# Flyback_schematic.net
KiCad netlist of a schematic drawn in Altium Designer
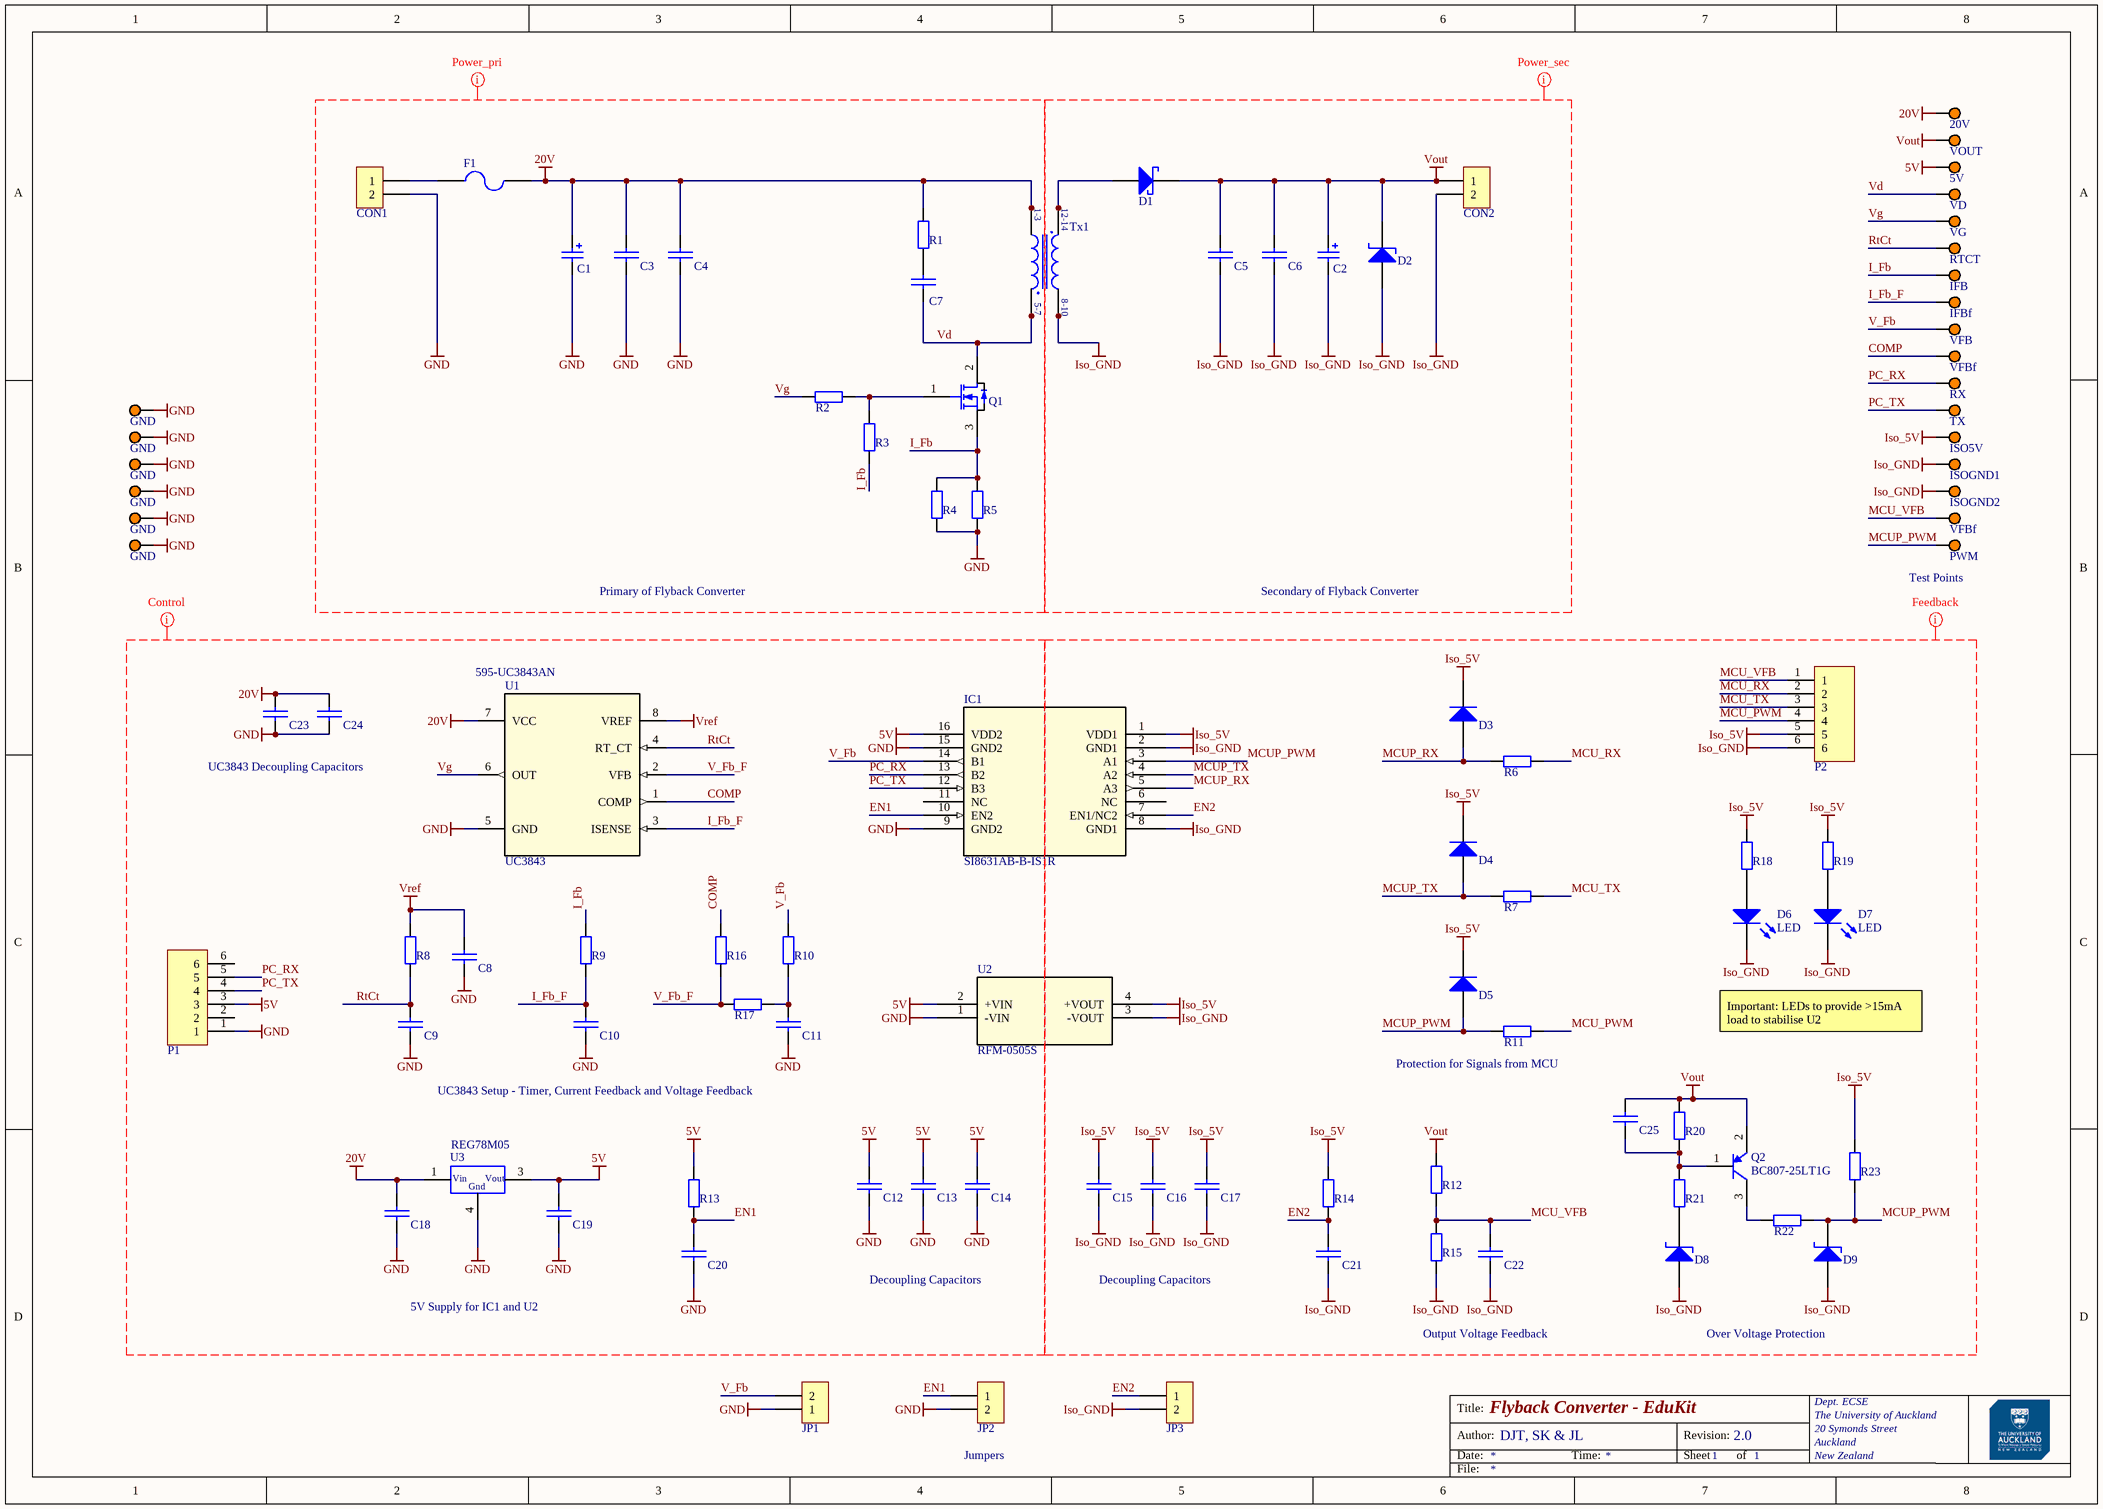
[diagram p0: Flyback_schematic.SchDoc]

(export (version "E")
  (design (tool "Eeschema 10.0.6"))
  (components
    (comp (ref "C1") (value "ECAP") (footprint "CR05") (libsource (lib "EE311_library") (part "ECAP")))
    (comp (ref "C2") (value "ECAP") (footprint "CR05") (libsource (lib "EE311_library") (part "ECAP")))
    (comp (ref "C3")
      (value "CCAP1210")
      (footprint "C1210")
      (libsource (lib "EE311_library") (part "CCAP1210"))
    )
    (comp (ref "C4")
      (value "CCAP1210")
      (footprint "C1210")
      (libsource (lib "EE311_library") (part "CCAP1210"))
    )
    (comp (ref "C5")
      (value "CCAP1210")
      (footprint "C1210")
      (libsource (lib "EE311_library") (part "CCAP1210"))
    )
    (comp (ref "C6")
      (value "CCAP1210")
      (footprint "C1210")
      (libsource (lib "EE311_library") (part "CCAP1210"))
    )
    (comp (ref "C7")
      (value "CCAP1210")
      (footprint "C1210")
      (libsource (lib "EE311_library") (part "CCAP1210"))
    )
    (comp (ref "C8")
      (value "Capacitor 0805")
      (footprint "C0805")
      (description "CCAP0805")
      (libsource (lib "EE311_library") (part "CCAP0805"))
    )
    (comp (ref "C9")
      (value "Capacitor 0805")
      (footprint "C0805")
      (description "CCAP0805")
      (libsource (lib "EE311_library") (part "CCAP0805"))
    )
    (comp (ref "C10")
      (value "Capacitor 0805")
      (footprint "C0805")
      (description "CCAP0805")
      (libsource (lib "EE311_library") (part "CCAP0805"))
    )
    (comp (ref "C11")
      (value "Capacitor 0805")
      (footprint "C0805")
      (description "CCAP0805")
      (libsource (lib "EE311_library") (part "CCAP0805"))
    )
    (comp (ref "C12")
      (value "Capacitor 0805")
      (footprint "C0805")
      (description "CCAP0805")
      (libsource (lib "EE311_library") (part "CCAP0805"))
    )
    (comp (ref "C13")
      (value "Capacitor 0805")
      (footprint "C0805")
      (description "CCAP0805")
      (libsource (lib "EE311_library") (part "CCAP0805"))
    )
    (comp (ref "C14")
      (value "Capacitor 0805")
      (footprint "C0805")
      (description "CCAP0805")
      (libsource (lib "EE311_library") (part "CCAP0805"))
    )
    (comp (ref "C15")
      (value "Capacitor 0805")
      (footprint "C0805")
      (description "CCAP0805")
      (libsource (lib "EE311_library") (part "CCAP0805"))
    )
    (comp (ref "C16")
      (value "Capacitor 0805")
      (footprint "C0805")
      (description "CCAP0805")
      (libsource (lib "EE311_library") (part "CCAP0805"))
    )
    (comp (ref "C17")
      (value "Capacitor 0805")
      (footprint "C0805")
      (description "CCAP0805")
      (libsource (lib "EE311_library") (part "CCAP0805"))
    )
    (comp (ref "C18")
      (value "Capacitor 0805")
      (footprint "C0805")
      (description "CCAP0805")
      (libsource (lib "EE311_library") (part "CCAP0805"))
    )
    (comp (ref "C19")
      (value "Capacitor 0805")
      (footprint "C0805")
      (description "CCAP0805")
      (libsource (lib "EE311_library") (part "CCAP0805"))
    )
    (comp (ref "C20")
      (value "Capacitor 0805")
      (footprint "C0805")
      (description "CCAP0805")
      (libsource (lib "EE311_library") (part "CCAP0805"))
    )
    (comp (ref "C21")
      (value "Capacitor 0805")
      (footprint "C0805")
      (description "CCAP0805")
      (libsource (lib "EE311_library") (part "CCAP0805"))
    )
    (comp (ref "C22")
      (value "Capacitor 0805")
      (footprint "C0805")
      (description "CCAP0805")
      (libsource (lib "EE311_library") (part "CCAP0805"))
    )
    (comp (ref "C23")
      (value "Capacitor 0805")
      (footprint "C0805")
      (description "CCAP0805")
      (libsource (lib "EE311_library") (part "CCAP0805"))
    )
    (comp (ref "C24")
      (value "Capacitor 0805")
      (footprint "C0805")
      (description "CCAP0805")
      (libsource (lib "EE311_library") (part "CCAP0805"))
    )
    (comp (ref "C25")
      (value "Capacitor 0805")
      (footprint "C0805")
      (description "CCAP0805")
      (libsource (lib "EE311_library") (part "CCAP0805"))
    )
    (comp (ref "CON1") (value "Header 2X1") (footprint "HDR2X1_5") (libsource (lib "") (part "HDR2X1_2")))
    (comp (ref "CON2")
      (value "Header 2X1")
      (footprint "HDR2X1_5")
      (libsource (lib "EE311_library") (part "HDR2X1"))
    )
    (comp (ref "D1")
      (value "SDT5H100P5")
      (footprint "PowerDI5")
      (description "Schottky Diode")
      (libsource (lib "EE311_library") (part "SDT5H100P5"))
    )
    (comp (ref "D2")
      (value "Zener")
      (footprint "SOD123")
      (description "Zener Diode")
      (libsource (lib "EE311_library") (part "Zener"))
    )
    (comp (ref "D3")
      (value "1N4148")
      (footprint "SOD123")
      (description "Signal Diode - 1N4148")
      (libsource (lib "EE311_library") (part "1N4148"))
    )
    (comp (ref "D4")
      (value "1N4148")
      (footprint "SOD123")
      (description "Signal Diode - 1N4148")
      (libsource (lib "EE311_library") (part "1N4148"))
    )
    (comp (ref "D5")
      (value "1N4148")
      (footprint "SOD123")
      (description "Signal Diode - 1N4148")
      (libsource (lib "EE311_library") (part "1N4148"))
    )
    (comp (ref "D6") (value "LED") (footprint "LED0805") (libsource (lib "EE311_library") (part "LED")))
    (comp (ref "D7") (value "LED") (footprint "LED0805") (libsource (lib "EE311_library") (part "LED")))
    (comp (ref "D8")
      (value "Zener")
      (footprint "SOD123")
      (description "Zener Diode")
      (libsource (lib "EE311_library") (part "Zener"))
    )
    (comp (ref "D9")
      (value "Zener")
      (footprint "SOD123")
      (description "Zener Diode")
      (libsource (lib "EE311_library") (part "Zener"))
    )
    (comp (ref "F1")
      (value "Fuse Resettable")
      (footprint "0ZCF Series")
      (description "PTC RESET FUSE 60V 1A 2920")
      (fields (field (name "MPN") "0ZCF0100AF2A") (field (name "MANUFACTURER") "Bel Fuse Inc."))
      (libsource (lib "EE311_library") (part "FuseResettable 0ZCF0100AF2A"))
    )
    (comp (ref "GND1")
      (value "GND")
      (footprint "Testpoint - 1mm")
      (description "Testpoint")
      (libsource (lib "EE311_symbols") (part "TP"))
    )
    (comp (ref "GND2")
      (value "GND")
      (footprint "Testpoint - 1mm")
      (description "Testpoint")
      (libsource (lib "EE311_symbols") (part "TP"))
    )
    (comp (ref "GND3")
      (value "GND")
      (footprint "Testpoint - 1mm")
      (description "Testpoint")
      (libsource (lib "EE311_symbols") (part "TP"))
    )
    (comp (ref "GND4")
      (value "GND")
      (footprint "Testpoint - 1mm")
      (description "Testpoint")
      (libsource (lib "EE311_symbols") (part "TP"))
    )
    (comp (ref "GND5")
      (value "GND")
      (footprint "Testpoint - 1mm")
      (description "Testpoint")
      (libsource (lib "EE311_symbols") (part "TP"))
    )
    (comp (ref "GND6")
      (value "GND")
      (footprint "Testpoint - 1mm")
      (description "Testpoint")
      (libsource (lib "EE311_symbols") (part "TP"))
    )
    (comp (ref "IC1")
      (value "SI8631AB-B-IS1R")
      (footprint "EE311_footprints:SOIC16")
      (description "No Description Available")
      (fields (field (name "COPYRIGHT") "Copyright (C) 2018 Accelerated Designs. All rights reserved"))
      (libsource (lib "EE311_symbols") (part "SI8631AB-B-IS1R"))
    )
    (comp (ref "JP1") (value "Header 2X1") (footprint "HDR2X1_2P54") (libsource (lib "") (part "HDR2X1_1")))
    (comp (ref "JP2")
      (value "Header 2X1")
      (footprint "HDR2X1_2P54")
      (libsource (lib "EE311_library") (part "HDR2X1"))
    )
    (comp (ref "JP3")
      (value "Header 2X1")
      (footprint "HDR2X1_2P54")
      (libsource (lib "EE311_library") (part "HDR2X1"))
    )
    (comp (ref "P1")
      (value "Header 6X1")
      (footprint "HDR6X1_2P54")
      (description "Header, 6-Pin")
      (fields (field (name "PUBLISHER") "Altium Limited"))
      (libsource (lib "") (part "HDR6X1_1"))
    )
    (comp (ref "P2")
      (value "Header 6X1")
      (footprint "HDR6X1_2P54")
      (description "Header, 6-Pin")
      (fields (field (name "PUBLISHER") "Altium Limited"))
      (libsource (lib "EE311_library") (part "HDR6X1"))
    )
    (comp (ref "Q1")
      (value "MOSFET")
      (footprint "TO220")
      (description "NFET TO220")
      (libsource (lib "EE311_symbols") (part "NFET1"))
    )
    (comp (ref "Q2")
      (value "BC807-25LT1G")
      (footprint "SOT23SM")
      (description "General Purpose Transistor, PNP Silicon, 3-Pin SOT-23, Pb-Free, Tape and Reel")
      (fields (field (name "MANUFACTURER") "On Semiconductor"))
      (libsource (lib "EE311_library") (part "BC807"))
    )
    (comp (ref "R1")
      (value "Resistor 1206")
      (footprint "R1206")
      (description "RES1206")
      (libsource (lib "EE311_library") (part "RES1206"))
    )
    (comp (ref "R2")
      (value "Resistor 0805")
      (footprint "R0805")
      (description "RES0805")
      (libsource (lib "") (part "RES0805_1"))
    )
    (comp (ref "R3")
      (value "Resistor 0805")
      (footprint "R0805")
      (description "RES0805")
      (libsource (lib "EE311_library") (part "RES0805"))
    )
    (comp (ref "R4")
      (value "Resistor 1206")
      (footprint "R1206")
      (description "RES1206")
      (libsource (lib "EE311_library") (part "RES1206"))
    )
    (comp (ref "R5")
      (value "Resistor 1206")
      (footprint "R1206")
      (description "RES1206")
      (libsource (lib "EE311_library") (part "RES1206"))
    )
    (comp (ref "R6")
      (value "Resistor 0805")
      (footprint "R0805")
      (description "RES0805")
      (libsource (lib "") (part "RES0805_2"))
    )
    (comp (ref "R7")
      (value "Resistor 0805")
      (footprint "R0805")
      (description "RES0805")
      (libsource (lib "") (part "RES0805_2"))
    )
    (comp (ref "R8")
      (value "Resistor 0805")
      (footprint "R0805")
      (description "RES0805")
      (libsource (lib "") (part "RES0805_3"))
    )
    (comp (ref "R9")
      (value "Resistor 0805")
      (footprint "R0805")
      (description "RES0805")
      (libsource (lib "EE311_library") (part "RES0805"))
    )
    (comp (ref "R10")
      (value "Resistor 0805")
      (footprint "R0805")
      (description "RES0805")
      (libsource (lib "EE311_library") (part "RES0805"))
    )
    (comp (ref "R11")
      (value "Resistor 0805")
      (footprint "R0805")
      (description "RES0805")
      (libsource (lib "") (part "RES0805_2"))
    )
    (comp (ref "R12")
      (value "Resistor 0805")
      (footprint "R0805")
      (description "RES0805")
      (libsource (lib "EE311_library") (part "RES0805"))
    )
    (comp (ref "R13")
      (value "Resistor 0805")
      (footprint "R0805")
      (description "RES0805")
      (libsource (lib "EE311_library") (part "RES0805"))
    )
    (comp (ref "R14")
      (value "Resistor 0805")
      (footprint "R0805")
      (description "RES0805")
      (libsource (lib "EE311_library") (part "RES0805"))
    )
    (comp (ref "R15")
      (value "Resistor 0805")
      (footprint "R0805")
      (description "RES0805")
      (libsource (lib "EE311_library") (part "RES0805"))
    )
    (comp (ref "R16")
      (value "Resistor 0805")
      (footprint "R0805")
      (description "RES0805")
      (libsource (lib "EE311_library") (part "RES0805"))
    )
    (comp (ref "R17")
      (value "Resistor 0805")
      (footprint "R0805")
      (description "RES0805")
      (libsource (lib "") (part "RES0805_2"))
    )
    (comp (ref "R18")
      (value "Resistor 0805")
      (footprint "R0805")
      (description "RES0805")
      (libsource (lib "EE311_library") (part "RES0805"))
    )
    (comp (ref "R19")
      (value "Resistor 0805")
      (footprint "R0805")
      (description "RES0805")
      (libsource (lib "EE311_library") (part "RES0805"))
    )
    (comp (ref "R20")
      (value "Resistor 0805")
      (footprint "R0805")
      (description "RES0805")
      (libsource (lib "EE311_library") (part "RES0805"))
    )
    (comp (ref "R21")
      (value "Resistor 0805")
      (footprint "R0805")
      (description "RES0805")
      (libsource (lib "EE311_library") (part "RES0805"))
    )
    (comp (ref "R22")
      (value "Resistor 0805")
      (footprint "R0805")
      (description "RES0805")
      (libsource (lib "") (part "RES0805_1"))
    )
    (comp (ref "R23")
      (value "Resistor 0805")
      (footprint "R0805")
      (description "RES0805")
      (libsource (lib "EE311_library") (part "RES0805"))
    )
    (comp (ref "TP1")
      (value "20V")
      (footprint "Testpoint - 1mm")
      (description "Testpoint")
      (libsource (lib "EE311_symbols") (part "TP"))
    )
    (comp (ref "TP2")
      (value "VOUT")
      (footprint "Testpoint - 1mm")
      (description "Testpoint")
      (libsource (lib "EE311_symbols") (part "TP"))
    )
    (comp (ref "TP3")
      (value "VG")
      (footprint "Testpoint - 1mm")
      (description "Testpoint")
      (libsource (lib "EE311_symbols") (part "TP"))
    )
    (comp (ref "TP4")
      (value "PWM")
      (footprint "Testpoint - 1mm")
      (description "Testpoint")
      (libsource (lib "EE311_symbols") (part "TP"))
    )
    (comp (ref "TP6")
      (value "IFB")
      (footprint "Testpoint - 1mm")
      (description "Testpoint")
      (libsource (lib "EE311_symbols") (part "TP"))
    )
    (comp (ref "TP7")
      (value "VFB")
      (footprint "Testpoint - 1mm")
      (description "Testpoint")
      (libsource (lib "EE311_symbols") (part "TP"))
    )
    (comp (ref "TP8")
      (value "RX")
      (footprint "Testpoint - 1mm")
      (description "Testpoint")
      (libsource (lib "EE311_symbols") (part "TP"))
    )
    (comp (ref "TP9")
      (value "5V")
      (footprint "Testpoint - 1mm")
      (description "Testpoint")
      (libsource (lib "EE311_symbols") (part "TP"))
    )
    (comp (ref "TP10")
      (value "ISO5V")
      (footprint "Testpoint - 1mm")
      (description "Testpoint")
      (libsource (lib "EE311_symbols") (part "TP"))
    )
    (comp (ref "TP11")
      (value "ISOGND1")
      (footprint "Testpoint - 1mm")
      (description "Testpoint")
      (libsource (lib "EE311_symbols") (part "TP"))
    )
    (comp (ref "TP12")
      (value "TX")
      (footprint "Testpoint - 1mm")
      (description "Testpoint")
      (libsource (lib "EE311_symbols") (part "TP"))
    )
    (comp (ref "TP13")
      (value "ISOGND2")
      (footprint "Testpoint - 1mm")
      (description "Testpoint")
      (libsource (lib "EE311_symbols") (part "TP"))
    )
    (comp (ref "TP14")
      (value "RTCT")
      (footprint "Testpoint - 1mm")
      (description "Testpoint")
      (libsource (lib "EE311_symbols") (part "TP"))
    )
    (comp (ref "TP15")
      (value "IFBf")
      (footprint "Testpoint - 1mm")
      (description "Testpoint")
      (libsource (lib "EE311_symbols") (part "TP"))
    )
    (comp (ref "TP16")
      (value "VFBf")
      (footprint "Testpoint - 1mm")
      (description "Testpoint")
      (libsource (lib "EE311_symbols") (part "TP"))
    )
    (comp (ref "TP17")
      (value "VFBf")
      (footprint "Testpoint - 1mm")
      (description "Testpoint")
      (libsource (lib "EE311_symbols") (part "TP"))
    )
    (comp (ref "Tx1")
      (value "Inductor")
      (footprint "ETD34")
      (description "Inductor with core")
      (libsource (lib "EE311_library") (part "Transformer EFD34"))
    )
    (comp (ref "U1")
      (value "UC3843")
      (footprint "DIP-8")
      (description "No Description Available")
      (fields
        (field (name "PARTNUMBER") "UC3843N")
        (field (name "MANUFACTURER") "Texas Instruments")
        (field (name "SUPPLIER PART NUMBER 1") "595-UC3843AN")
        (field (name "COPYRIGHT") "Copyright (C) 2018 Accelerated Designs. All rights reserved")
      )
      (libsource (lib "EE311_library") (part "UC3843"))
    )
    (comp (ref "U2")
      (value "RFM-0505S")
      (footprint "RFM-0505S_RCP")
      (description "No Description Available")
      (fields (field (name "COPYRIGHT") "Copyright (C) 2018 Accelerated Designs. All rights reserved"))
      (libsource (lib "EE311_library") (part "RFM-0505S"))
    )
    (comp (ref "U3")
      (value "REG78M05")
      (footprint "TO252")
      (description "78M Series Linear Regulators")
      (libsource (lib "EE311_library") (part "REG78MXX"))
    )
    (comp (ref "VD")
      (value "VD")
      (footprint "Testpoint - 1mm")
      (description "Testpoint")
      (libsource (lib "EE311_symbols") (part "TP"))
    )
  )
  (nets
    (net (code "1") (name "/COMP") (class "Default")
      (node (ref "R16") (pin "2") (pinfunction "2_2") (pintype "passive"))
      (node (ref "TP16") (pin "1") (pinfunction "1_1") (pintype "passive"))
      (node (ref "U1") (pin "1") (pinfunction "COMP_1") (pintype "output"))
    )
    (net (code "2") (name "/EN1") (class "Default")
      (node (ref "C20") (pin "2") (pinfunction "2_2") (pintype "passive"))
      (node (ref "IC1") (pin "10") (pinfunction "EN2_10") (pintype "input"))
      (node (ref "JP2") (pin "1") (pinfunction "1_1") (pintype "passive"))
      (node (ref "R13") (pin "1") (pinfunction "1_1") (pintype "passive"))
    )
    (net (code "3") (name "/EN2") (class "Default")
      (node (ref "C21") (pin "2") (pinfunction "2_2") (pintype "passive"))
      (node (ref "IC1") (pin "7") (pinfunction "EN1/NC2_7") (pintype "input"))
      (node (ref "JP3") (pin "1") (pinfunction "1_1") (pintype "passive"))
      (node (ref "R14") (pin "1") (pinfunction "1_1") (pintype "passive"))
    )
    (net (code "4") (name "/I_Fb") (class "Default")
      (node (ref "Q1") (pin "3") (pinfunction "S_3") (pintype "passive"))
      (node (ref "R3") (pin "1") (pinfunction "1_1") (pintype "passive"))
      (node (ref "R4") (pin "2") (pinfunction "2_2") (pintype "passive"))
      (node (ref "R5") (pin "2") (pinfunction "2_2") (pintype "passive"))
      (node (ref "R9") (pin "2") (pinfunction "2_2") (pintype "passive"))
      (node (ref "TP6") (pin "1") (pinfunction "1_1") (pintype "passive"))
    )
    (net (code "5") (name "/I_Fb_F") (class "Default")
      (node (ref "C10") (pin "2") (pinfunction "2_2") (pintype "passive"))
      (node (ref "R9") (pin "1") (pinfunction "1_1") (pintype "passive"))
      (node (ref "TP15") (pin "1") (pinfunction "1_1") (pintype "passive"))
      (node (ref "U1") (pin "3") (pinfunction "ISENSE_3") (pintype "input"))
    )
    (net (code "6") (name "/MCUP_PWM") (class "Default")
      (node (ref "D5") (pin "1") (pinfunction "1_1") (pintype "passive"))
      (node (ref "D9") (pin "2") (pinfunction "K_2") (pintype "passive"))
      (node (ref "IC1") (pin "3") (pinfunction "A1_3") (pintype "input"))
      (node (ref "R11") (pin "2") (pinfunction "2_2") (pintype "passive"))
      (node (ref "R22") (pin "2") (pinfunction "2_2") (pintype "passive"))
      (node (ref "R23") (pin "1") (pinfunction "1_1") (pintype "passive"))
      (node (ref "TP4") (pin "1") (pinfunction "1_1") (pintype "passive"))
    )
    (net (code "7") (name "/MCUP_RX") (class "Default")
      (node (ref "D3") (pin "1") (pinfunction "1_1") (pintype "passive"))
      (node (ref "IC1") (pin "5") (pinfunction "A3_5") (pintype "output"))
      (node (ref "R6") (pin "2") (pinfunction "2_2") (pintype "passive"))
    )
    (net (code "8") (name "/MCUP_TX") (class "Default")
      (node (ref "D4") (pin "1") (pinfunction "1_1") (pintype "passive"))
      (node (ref "IC1") (pin "4") (pinfunction "A2_4") (pintype "input"))
      (node (ref "R7") (pin "2") (pinfunction "2_2") (pintype "passive"))
    )
    (net (code "9") (name "/MCU_PWM") (class "Default")
      (node (ref "P2") (pin "4") (pinfunction "4_4") (pintype "passive"))
      (node (ref "R11") (pin "1") (pinfunction "1_1") (pintype "passive"))
    )
    (net (code "10") (name "/MCU_RX") (class "Default")
      (node (ref "P2") (pin "2") (pinfunction "2_2") (pintype "passive"))
      (node (ref "R6") (pin "1") (pinfunction "1_1") (pintype "passive"))
    )
    (net (code "11") (name "/MCU_TX") (class "Default")
      (node (ref "P2") (pin "3") (pinfunction "3_3") (pintype "passive"))
      (node (ref "R7") (pin "1") (pinfunction "1_1") (pintype "passive"))
    )
    (net (code "12") (name "/MCU_VFB") (class "Default")
      (node (ref "C22") (pin "2") (pinfunction "2_2") (pintype "passive"))
      (node (ref "P2") (pin "1") (pinfunction "1_1") (pintype "passive"))
      (node (ref "R12") (pin "1") (pinfunction "1_1") (pintype "passive"))
      (node (ref "R15") (pin "2") (pinfunction "2_2") (pintype "passive"))
      (node (ref "TP17") (pin "1") (pinfunction "1_1") (pintype "passive"))
    )
    (net (code "13") (name "/PC_RX") (class "Default")
      (node (ref "IC1") (pin "13") (pinfunction "B2_13") (pintype "output"))
      (node (ref "P1") (pin "5") (pinfunction "5_5") (pintype "passive"))
      (node (ref "TP8") (pin "1") (pinfunction "1_1") (pintype "passive"))
    )
    (net (code "14") (name "/PC_TX") (class "Default")
      (node (ref "IC1") (pin "12") (pinfunction "B3_12") (pintype "input"))
      (node (ref "P1") (pin "4") (pinfunction "4_4") (pintype "passive"))
      (node (ref "TP12") (pin "1") (pinfunction "1_1") (pintype "passive"))
    )
    (net (code "15") (name "/RtCt") (class "Default")
      (node (ref "C9") (pin "2") (pinfunction "2_2") (pintype "passive"))
      (node (ref "R8") (pin "2") (pinfunction "2_2") (pintype "passive"))
      (node (ref "TP14") (pin "1") (pinfunction "1_1") (pintype "passive"))
      (node (ref "U1") (pin "4") (pinfunction "RT_CT_4") (pintype "input"))
    )
    (net (code "16") (name "/V_Fb") (class "Default")
      (node (ref "IC1") (pin "14") (pinfunction "B1_14") (pintype "output"))
      (node (ref "JP1") (pin "2") (pinfunction "2_2") (pintype "passive"))
      (node (ref "R10") (pin "2") (pinfunction "2_2") (pintype "passive"))
      (node (ref "TP7") (pin "1") (pinfunction "1_1") (pintype "passive"))
    )
    (net (code "17") (name "/V_Fb_F") (class "Default")
      (node (ref "R16") (pin "1") (pinfunction "1_1") (pintype "passive"))
      (node (ref "R17") (pin "2") (pinfunction "2_2") (pintype "passive"))
      (node (ref "U1") (pin "2") (pinfunction "VFB_2") (pintype "input"))
    )
    (net (code "18") (name "/Vd") (class "Default")
      (node (ref "C7") (pin "1") (pinfunction "1_1") (pintype "passive"))
      (node (ref "Q1") (pin "2") (pinfunction "D_2") (pintype "passive"))
      (node (ref "Tx1") (pin "5") (pinfunction "5_5") (pintype "passive"))
      (node (ref "Tx1") (pin "6") (pinfunction "6_6") (pintype "passive"))
      (node (ref "Tx1") (pin "7") (pinfunction "7_7") (pintype "passive"))
      (node (ref "VD") (pin "1") (pinfunction "1_1") (pintype "passive"))
    )
    (net (code "19") (name "/Vg") (class "Default")
      (node (ref "R2") (pin "1") (pinfunction "1_1") (pintype "passive"))
      (node (ref "TP3") (pin "1") (pinfunction "1_1") (pintype "passive"))
      (node (ref "U1") (pin "6") (pinfunction "OUT_6") (pintype "output"))
    )
    (net (code "20") (name "5V") (class "Default")
      (node (ref "C12") (pin "2") (pinfunction "2_2") (pintype "passive"))
      (node (ref "C13") (pin "2") (pinfunction "2_2") (pintype "passive"))
      (node (ref "C14") (pin "2") (pinfunction "2_2") (pintype "passive"))
      (node (ref "C19") (pin "2") (pinfunction "2_2") (pintype "passive"))
      (node (ref "IC1") (pin "16") (pinfunction "VDD2_16") (pintype "power_in"))
      (node (ref "P1") (pin "3") (pinfunction "3_3") (pintype "passive"))
      (node (ref "R13") (pin "2") (pinfunction "2_2") (pintype "passive"))
      (node (ref "TP9") (pin "1") (pinfunction "1_1") (pintype "passive"))
      (node (ref "U2") (pin "2") (pinfunction "+VIN_2") (pintype "power_in"))
      (node (ref "U3") (pin "3") (pinfunction "Vout_3") (pintype "passive"))
    )
    (net (code "21") (name "20V") (class "Default")
      (node (ref "C1") (pin "1") (pinfunction "1_1") (pintype "passive"))
      (node (ref "C18") (pin "2") (pinfunction "2_2") (pintype "passive"))
      (node (ref "C23") (pin "2") (pinfunction "2_2") (pintype "passive"))
      (node (ref "C24") (pin "2") (pinfunction "2_2") (pintype "passive"))
      (node (ref "C3") (pin "2") (pinfunction "2_2") (pintype "passive"))
      (node (ref "C4") (pin "2") (pinfunction "2_2") (pintype "passive"))
      (node (ref "F1") (pin "2") (pinfunction "2_2") (pintype "passive"))
      (node (ref "R1") (pin "2") (pinfunction "2_2") (pintype "passive"))
      (node (ref "TP1") (pin "1") (pinfunction "1_1") (pintype "passive"))
      (node (ref "Tx1") (pin "1") (pinfunction "1_1") (pintype "passive"))
      (node (ref "Tx1") (pin "2") (pinfunction "2_2") (pintype "passive"))
      (node (ref "Tx1") (pin "3") (pinfunction "3_3") (pintype "passive"))
      (node (ref "U1") (pin "7") (pinfunction "VCC_7") (pintype "power_in"))
      (node (ref "U3") (pin "1") (pinfunction "Vin_1") (pintype "passive"))
    )
    (net (code "22") (name "GND") (class "Default")
      (node (ref "C1") (pin "2") (pinfunction "2_2") (pintype "passive"))
      (node (ref "C10") (pin "1") (pinfunction "1_1") (pintype "passive"))
      (node (ref "C11") (pin "1") (pinfunction "1_1") (pintype "passive"))
      (node (ref "C12") (pin "1") (pinfunction "1_1") (pintype "passive"))
      (node (ref "C13") (pin "1") (pinfunction "1_1") (pintype "passive"))
      (node (ref "C14") (pin "1") (pinfunction "1_1") (pintype "passive"))
      (node (ref "C18") (pin "1") (pinfunction "1_1") (pintype "passive"))
      (node (ref "C19") (pin "1") (pinfunction "1_1") (pintype "passive"))
      (node (ref "C20") (pin "1") (pinfunction "1_1") (pintype "passive"))
      (node (ref "C23") (pin "1") (pinfunction "1_1") (pintype "passive"))
      (node (ref "C24") (pin "1") (pinfunction "1_1") (pintype "passive"))
      (node (ref "C3") (pin "1") (pinfunction "1_1") (pintype "passive"))
      (node (ref "C4") (pin "1") (pinfunction "1_1") (pintype "passive"))
      (node (ref "C8") (pin "1") (pinfunction "1_1") (pintype "passive"))
      (node (ref "C9") (pin "1") (pinfunction "1_1") (pintype "passive"))
      (node (ref "CON1") (pin "2") (pinfunction "2_2") (pintype "passive"))
      (node (ref "GND1") (pin "1") (pinfunction "1_1") (pintype "passive"))
      (node (ref "GND2") (pin "1") (pinfunction "1_1") (pintype "passive"))
      (node (ref "GND3") (pin "1") (pinfunction "1_1") (pintype "passive"))
      (node (ref "GND4") (pin "1") (pinfunction "1_1") (pintype "passive"))
      (node (ref "GND5") (pin "1") (pinfunction "1_1") (pintype "passive"))
      (node (ref "GND6") (pin "1") (pinfunction "1_1") (pintype "passive"))
      (node (ref "IC1") (pin "15") (pinfunction "GND2_15") (pintype "passive"))
      (node (ref "IC1") (pin "9") (pinfunction "GND2_9") (pintype "passive"))
      (node (ref "JP1") (pin "1") (pinfunction "1_1") (pintype "passive"))
      (node (ref "JP2") (pin "2") (pinfunction "2_2") (pintype "passive"))
      (node (ref "P1") (pin "1") (pinfunction "1_1") (pintype "passive"))
      (node (ref "R4") (pin "1") (pinfunction "1_1") (pintype "passive"))
      (node (ref "R5") (pin "1") (pinfunction "1_1") (pintype "passive"))
      (node (ref "U1") (pin "5") (pinfunction "GND_5") (pintype "power_in"))
      (node (ref "U2") (pin "1") (pinfunction "-VIN_1") (pintype "passive"))
      (node (ref "U3") (pin "4") (pinfunction "Gnd_4") (pintype "passive"))
    )
    (net (code "23") (name "Iso_5V") (class "Default")
      (node (ref "C15") (pin "2") (pinfunction "2_2") (pintype "passive"))
      (node (ref "C16") (pin "2") (pinfunction "2_2") (pintype "passive"))
      (node (ref "C17") (pin "2") (pinfunction "2_2") (pintype "passive"))
      (node (ref "D3") (pin "2") (pinfunction "2_2") (pintype "passive"))
      (node (ref "D4") (pin "2") (pinfunction "2_2") (pintype "passive"))
      (node (ref "D5") (pin "2") (pinfunction "2_2") (pintype "passive"))
      (node (ref "IC1") (pin "1") (pinfunction "VDD1_1") (pintype "power_in"))
      (node (ref "P2") (pin "5") (pinfunction "5_5") (pintype "passive"))
      (node (ref "R14") (pin "2") (pinfunction "2_2") (pintype "passive"))
      (node (ref "R18") (pin "2") (pinfunction "2_2") (pintype "passive"))
      (node (ref "R19") (pin "2") (pinfunction "2_2") (pintype "passive"))
      (node (ref "R23") (pin "2") (pinfunction "2_2") (pintype "passive"))
      (node (ref "TP10") (pin "1") (pinfunction "1_1") (pintype "passive"))
      (node (ref "U2") (pin "4") (pinfunction "+VOUT_4") (pintype "power_in"))
    )
    (net (code "24") (name "Iso_GND") (class "Default")
      (node (ref "C15") (pin "1") (pinfunction "1_1") (pintype "passive"))
      (node (ref "C16") (pin "1") (pinfunction "1_1") (pintype "passive"))
      (node (ref "C17") (pin "1") (pinfunction "1_1") (pintype "passive"))
      (node (ref "C2") (pin "2") (pinfunction "2_2") (pintype "passive"))
      (node (ref "C21") (pin "1") (pinfunction "1_1") (pintype "passive"))
      (node (ref "C22") (pin "1") (pinfunction "1_1") (pintype "passive"))
      (node (ref "C5") (pin "1") (pinfunction "1_1") (pintype "passive"))
      (node (ref "C6") (pin "1") (pinfunction "1_1") (pintype "passive"))
      (node (ref "CON2") (pin "2") (pinfunction "2_2") (pintype "passive"))
      (node (ref "D2") (pin "1") (pinfunction "A_1") (pintype "passive"))
      (node (ref "D6") (pin "2") (pinfunction "K_2") (pintype "passive"))
      (node (ref "D7") (pin "2") (pinfunction "K_2") (pintype "passive"))
      (node (ref "D8") (pin "1") (pinfunction "A_1") (pintype "passive"))
      (node (ref "D9") (pin "1") (pinfunction "A_1") (pintype "passive"))
      (node (ref "IC1") (pin "2") (pinfunction "GND1_2") (pintype "passive"))
      (node (ref "IC1") (pin "8") (pinfunction "GND1_8") (pintype "passive"))
      (node (ref "JP3") (pin "2") (pinfunction "2_2") (pintype "passive"))
      (node (ref "P2") (pin "6") (pinfunction "6_6") (pintype "passive"))
      (node (ref "R15") (pin "1") (pinfunction "1_1") (pintype "passive"))
      (node (ref "TP11") (pin "1") (pinfunction "1_1") (pintype "passive"))
      (node (ref "TP13") (pin "1") (pinfunction "1_1") (pintype "passive"))
      (node (ref "Tx1") (pin "10") (pinfunction "10_10") (pintype "passive"))
      (node (ref "Tx1") (pin "8") (pinfunction "8_8") (pintype "passive"))
      (node (ref "Tx1") (pin "9") (pinfunction "9_9") (pintype "passive"))
      (node (ref "U2") (pin "3") (pinfunction "-VOUT_3") (pintype "passive"))
    )
    (net (code "25") (name "Net-(C7-Pad2)") (class "Default")
      (node (ref "C7") (pin "2") (pinfunction "2_2") (pintype "passive"))
      (node (ref "R1") (pin "1") (pinfunction "1_1") (pintype "passive"))
    )
    (net (code "26") (name "Net-(C11-Pad2)") (class "Default")
      (node (ref "C11") (pin "2") (pinfunction "2_2") (pintype "passive"))
      (node (ref "R10") (pin "1") (pinfunction "1_1") (pintype "passive"))
      (node (ref "R17") (pin "1") (pinfunction "1_1") (pintype "passive"))
    )
    (net (code "27") (name "Net-(CON1-Pad1)") (class "Default")
      (node (ref "CON1") (pin "1") (pinfunction "1_1") (pintype "passive"))
      (node (ref "F1") (pin "1") (pinfunction "1_1") (pintype "passive"))
    )
    (net (code "28") (name "Net-(D1-A)") (class "Default")
      (node (ref "D1") (pin "1") (pinfunction "A_1") (pintype "passive"))
      (node (ref "Tx1") (pin "12") (pinfunction "12_12") (pintype "passive"))
      (node (ref "Tx1") (pin "13") (pinfunction "13_13") (pintype "passive"))
      (node (ref "Tx1") (pin "14") (pinfunction "14_14") (pintype "passive"))
    )
    (net (code "29") (name "Net-(D6-A)") (class "Default")
      (node (ref "D6") (pin "1") (pinfunction "A_1") (pintype "passive"))
      (node (ref "R18") (pin "1") (pinfunction "1_1") (pintype "passive"))
    )
    (net (code "30") (name "Net-(D7-A)") (class "Default")
      (node (ref "D7") (pin "1") (pinfunction "A_1") (pintype "passive"))
      (node (ref "R19") (pin "1") (pinfunction "1_1") (pintype "passive"))
    )
    (net (code "31") (name "Net-(D8-K)") (class "Default")
      (node (ref "D8") (pin "2") (pinfunction "K_2") (pintype "passive"))
      (node (ref "R21") (pin "1") (pinfunction "1_1") (pintype "passive"))
    )
    (net (code "32") (name "Net-(Q1-G)") (class "Default")
      (node (ref "Q1") (pin "1") (pinfunction "G_1") (pintype "passive"))
      (node (ref "R2") (pin "2") (pinfunction "2_2") (pintype "passive"))
      (node (ref "R3") (pin "2") (pinfunction "2_2") (pintype "passive"))
    )
    (net (code "33") (name "Net-(Q2-B)") (class "Default")
      (node (ref "C25") (pin "1") (pinfunction "1_1") (pintype "passive"))
      (node (ref "Q2") (pin "1") (pinfunction "B_1") (pintype "passive"))
      (node (ref "R20") (pin "1") (pinfunction "1_1") (pintype "passive"))
      (node (ref "R21") (pin "2") (pinfunction "2_2") (pintype "passive"))
    )
    (net (code "34") (name "Net-(Q2-C)") (class "Default")
      (node (ref "Q2") (pin "3") (pinfunction "C_3") (pintype "passive"))
      (node (ref "R22") (pin "1") (pinfunction "1_1") (pintype "passive"))
    )
    (net (code "35") (name "Vout") (class "Default")
      (node (ref "C2") (pin "1") (pinfunction "1_1") (pintype "passive"))
      (node (ref "C25") (pin "2") (pinfunction "2_2") (pintype "passive"))
      (node (ref "C5") (pin "2") (pinfunction "2_2") (pintype "passive"))
      (node (ref "C6") (pin "2") (pinfunction "2_2") (pintype "passive"))
      (node (ref "CON2") (pin "1") (pinfunction "1_1") (pintype "passive"))
      (node (ref "D1") (pin "3") (pinfunction "K_3") (pintype "passive"))
      (node (ref "D2") (pin "2") (pinfunction "K_2") (pintype "passive"))
      (node (ref "Q2") (pin "2") (pinfunction "E_2") (pintype "passive"))
      (node (ref "R12") (pin "2") (pinfunction "2_2") (pintype "passive"))
      (node (ref "R20") (pin "2") (pinfunction "2_2") (pintype "passive"))
      (node (ref "TP2") (pin "1") (pinfunction "1_1") (pintype "passive"))
    )
    (net (code "36") (name "Vref") (class "Default")
      (node (ref "C8") (pin "2") (pinfunction "2_2") (pintype "passive"))
      (node (ref "R8") (pin "1") (pinfunction "1_1") (pintype "passive"))
      (node (ref "U1") (pin "8") (pinfunction "VREF_8") (pintype "power_in"))
    )
    (net (code "37") (name "unconnected-(IC1-NC-Pad6)") (class "Default")
      (node (ref "IC1") (pin "6") (pinfunction "NC_6") (pintype "passive"))
    )
    (net (code "38") (name "unconnected-(IC1-NC-Pad11)") (class "Default")
      (node (ref "IC1") (pin "11") (pinfunction "NC_11") (pintype "passive"))
    )
    (net (code "39") (name "unconnected-(P1-Pad2)") (class "Default")
      (node (ref "P1") (pin "2") (pinfunction "2_2") (pintype "passive"))
    )
    (net (code "40") (name "unconnected-(P1-Pad6)") (class "Default")
      (node (ref "P1") (pin "6") (pinfunction "6_6") (pintype "passive"))
    )
  )
)
